# SparkFun_SOIC20_Adapter_v10.net
KiCad netlist of a schematic drawn in EAGLE
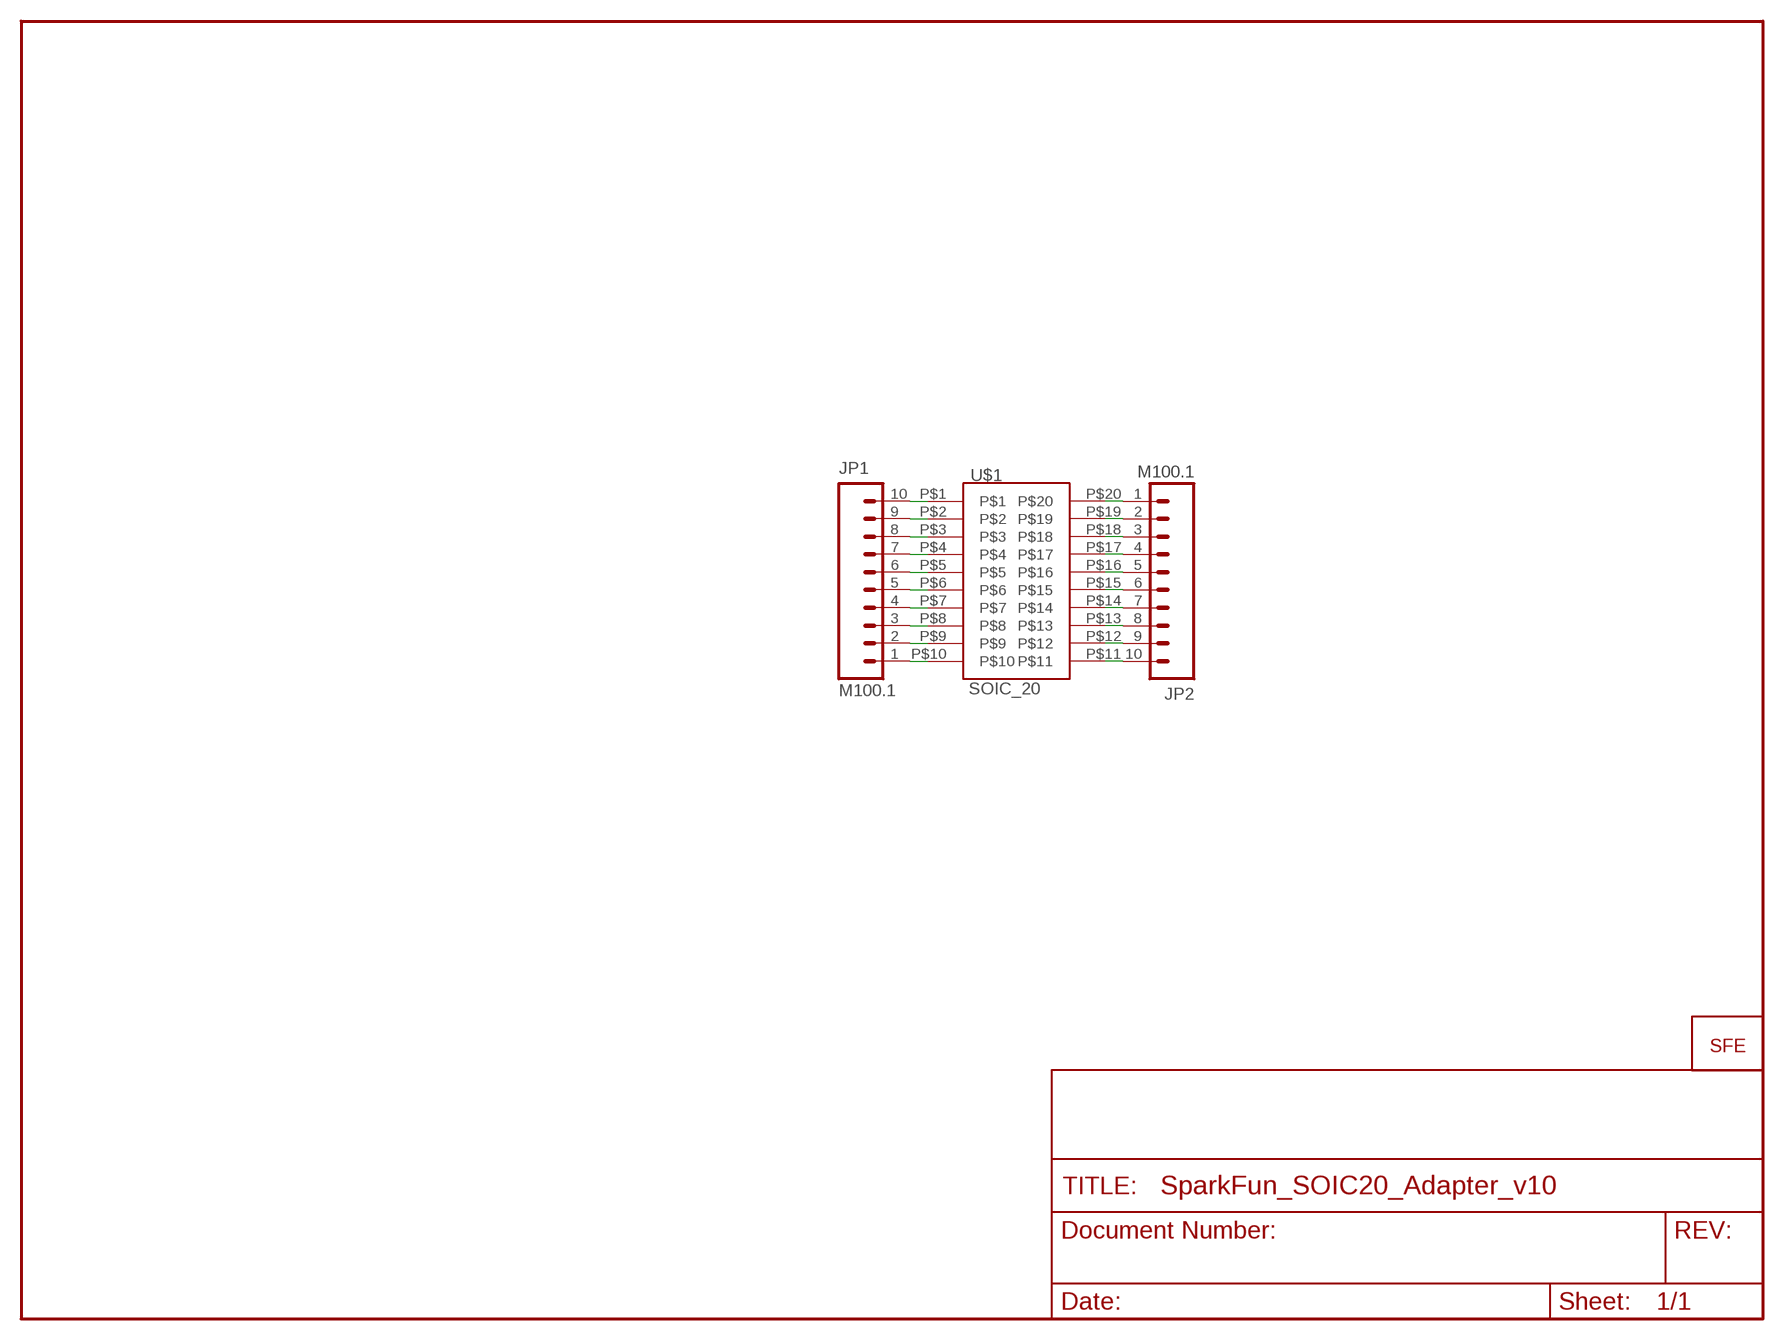
[diagram p0: schematic, sheet 1]

(export (version "E")
  (design (tool "Eeschema 10.0.6"))
  (components
    (comp (ref "JP1")
      (value "M100.1")
      (footprint "eagle-import:1X10")
      (libsource (lib "eagle-import") (part "M100.1"))
    )
    (comp (ref "JP2")
      (value "M100.1")
      (footprint "eagle-import:1X10")
      (libsource (lib "eagle-import") (part "M100.1"))
    )
    (comp (ref "U$1")
      (value "SOIC_20")
      (footprint "eagle-import:SO20W")
      (libsource (lib "eagle-import") (part "SOIC_20"))
    )
    (comp (ref "U$2")
      (value "LOGO-SFENEW")
      (footprint "eagle-import:SFE-NEW-WEBLOGO")
      (libsource (lib "eagle-import") (part "LOGO-SFENEW"))
    )
  )
  (nets
    (net (code "1") (name "Net-(JP1-Pad1)") (class "Default")
      (node (ref "JP1") (pin "1") (pinfunction "1_1") (pintype "passive"))
      (node (ref "U$1") (pin "P$10") (pinfunction "P$10_P$10") (pintype "bidirectional"))
    )
    (net (code "2") (name "Net-(JP1-Pad2)") (class "Default")
      (node (ref "JP1") (pin "2") (pinfunction "2_2") (pintype "passive"))
      (node (ref "U$1") (pin "P$9") (pinfunction "P$9_P$9") (pintype "bidirectional"))
    )
    (net (code "3") (name "Net-(JP1-Pad3)") (class "Default")
      (node (ref "JP1") (pin "3") (pinfunction "3_3") (pintype "passive"))
      (node (ref "U$1") (pin "P$8") (pinfunction "P$8_P$8") (pintype "bidirectional"))
    )
    (net (code "4") (name "Net-(JP1-Pad4)") (class "Default")
      (node (ref "JP1") (pin "4") (pinfunction "4_4") (pintype "passive"))
      (node (ref "U$1") (pin "P$7") (pinfunction "P$7_P$7") (pintype "bidirectional"))
    )
    (net (code "5") (name "Net-(JP1-Pad5)") (class "Default")
      (node (ref "JP1") (pin "5") (pinfunction "5_5") (pintype "passive"))
      (node (ref "U$1") (pin "P$6") (pinfunction "P$6_P$6") (pintype "bidirectional"))
    )
    (net (code "6") (name "Net-(JP1-Pad6)") (class "Default")
      (node (ref "JP1") (pin "6") (pinfunction "6_6") (pintype "passive"))
      (node (ref "U$1") (pin "P$5") (pinfunction "P$5_P$5") (pintype "bidirectional"))
    )
    (net (code "7") (name "Net-(JP1-Pad7)") (class "Default")
      (node (ref "JP1") (pin "7") (pinfunction "7_7") (pintype "passive"))
      (node (ref "U$1") (pin "P$4") (pinfunction "P$4_P$4") (pintype "bidirectional"))
    )
    (net (code "8") (name "Net-(JP1-Pad8)") (class "Default")
      (node (ref "JP1") (pin "8") (pinfunction "8_8") (pintype "passive"))
      (node (ref "U$1") (pin "P$3") (pinfunction "P$3_P$3") (pintype "bidirectional"))
    )
    (net (code "9") (name "Net-(JP1-Pad9)") (class "Default")
      (node (ref "JP1") (pin "9") (pinfunction "9_9") (pintype "passive"))
      (node (ref "U$1") (pin "P$2") (pinfunction "P$2_P$2") (pintype "bidirectional"))
    )
    (net (code "10") (name "Net-(JP1-Pad10)") (class "Default")
      (node (ref "JP1") (pin "10") (pinfunction "10_10") (pintype "passive"))
      (node (ref "U$1") (pin "P$1") (pinfunction "P$1_P$1") (pintype "bidirectional"))
    )
    (net (code "11") (name "Net-(JP2-Pad1)") (class "Default")
      (node (ref "JP2") (pin "1") (pinfunction "1_1") (pintype "passive"))
      (node (ref "U$1") (pin "P$20") (pinfunction "P$20_P$20") (pintype "bidirectional"))
    )
    (net (code "12") (name "Net-(JP2-Pad2)") (class "Default")
      (node (ref "JP2") (pin "2") (pinfunction "2_2") (pintype "passive"))
      (node (ref "U$1") (pin "P$19") (pinfunction "P$19_P$19") (pintype "bidirectional"))
    )
    (net (code "13") (name "Net-(JP2-Pad3)") (class "Default")
      (node (ref "JP2") (pin "3") (pinfunction "3_3") (pintype "passive"))
      (node (ref "U$1") (pin "P$18") (pinfunction "P$18_P$18") (pintype "bidirectional"))
    )
    (net (code "14") (name "Net-(JP2-Pad4)") (class "Default")
      (node (ref "JP2") (pin "4") (pinfunction "4_4") (pintype "passive"))
      (node (ref "U$1") (pin "P$17") (pinfunction "P$17_P$17") (pintype "bidirectional"))
    )
    (net (code "15") (name "Net-(JP2-Pad5)") (class "Default")
      (node (ref "JP2") (pin "5") (pinfunction "5_5") (pintype "passive"))
      (node (ref "U$1") (pin "P$16") (pinfunction "P$16_P$16") (pintype "bidirectional"))
    )
    (net (code "16") (name "Net-(JP2-Pad6)") (class "Default")
      (node (ref "JP2") (pin "6") (pinfunction "6_6") (pintype "passive"))
      (node (ref "U$1") (pin "P$15") (pinfunction "P$15_P$15") (pintype "bidirectional"))
    )
    (net (code "17") (name "Net-(JP2-Pad7)") (class "Default")
      (node (ref "JP2") (pin "7") (pinfunction "7_7") (pintype "passive"))
      (node (ref "U$1") (pin "P$14") (pinfunction "P$14_P$14") (pintype "bidirectional"))
    )
    (net (code "18") (name "Net-(JP2-Pad8)") (class "Default")
      (node (ref "JP2") (pin "8") (pinfunction "8_8") (pintype "passive"))
      (node (ref "U$1") (pin "P$13") (pinfunction "P$13_P$13") (pintype "bidirectional"))
    )
    (net (code "19") (name "Net-(JP2-Pad9)") (class "Default")
      (node (ref "JP2") (pin "9") (pinfunction "9_9") (pintype "passive"))
      (node (ref "U$1") (pin "P$12") (pinfunction "P$12_P$12") (pintype "bidirectional"))
    )
    (net (code "20") (name "Net-(JP2-Pad10)") (class "Default")
      (node (ref "JP2") (pin "10") (pinfunction "10_10") (pintype "passive"))
      (node (ref "U$1") (pin "P$11") (pinfunction "P$11_P$11") (pintype "bidirectional"))
    )
  )
)
